# SRAM.net
KiCad netlist of a schematic drawn in Altium Designer
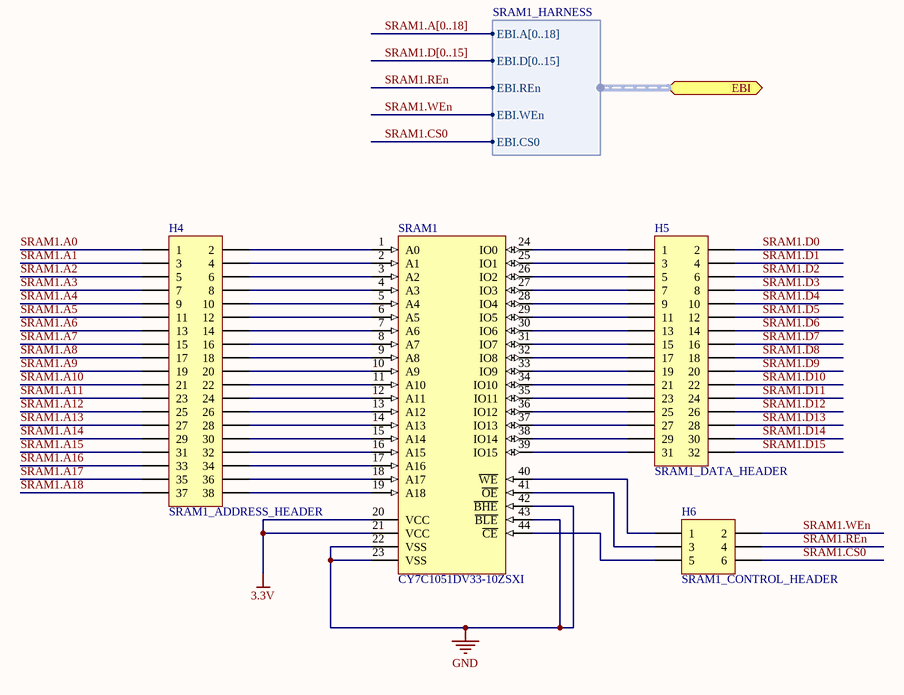
[diagram p0: SRAM.SchDoc]

(export (version "E")
  (design (tool "Eeschema 10.0.6"))
  (components
    (comp (ref "H4")
      (value "SRAM1_ADDRESS_HEADER")
      (footprint "HDR2X19")
      (description "Header, 19-Pin, Dual row")
      (fields (field (name "PUBLISHER") "Altium Limited"))
      (libsource (lib "Miscellaneous Connectors") (part "Header 19X2"))
    )
    (comp (ref "H5")
      (value "SRAM1_DATA_HEADER")
      (footprint "HDR2X16")
      (description "Header, 16-Pin, Dual row")
      (fields (field (name "PUBLISHER") "Altium Limited"))
      (libsource (lib "Miscellaneous Connectors") (part "Header 16X2"))
    )
    (comp (ref "H6")
      (value "SRAM1_CONTROL_HEADER")
      (footprint "HDR2X3")
      (description "Header, 3-Pin, Dual row")
      (fields (field (name "PUBLISHER") "Altium Limited"))
      (libsource (lib "Miscellaneous Connectors") (part "Header 3X2"))
    )
    (comp (ref "SRAM1")
      (value "CY7C1051DV33-10ZSXI")
      (footprint "TSOP-44-SRAM")
      (libsource (lib "Vector Library") (part "CY7C1051DV33-10ZSXI"))
    )
  )
  (nets
    (net (code "3") (name "/SRAM1.A0") (class "Default")
      (node (ref "H4") (pin "1") (pinfunction "1_1") (pintype "passive"))
    )
    (net (code "4") (name "/SRAM1.A1") (class "Default")
      (node (ref "H4") (pin "3") (pinfunction "3_3") (pintype "passive"))
    )
    (net (code "5") (name "/SRAM1.A2") (class "Default")
      (node (ref "H4") (pin "5") (pinfunction "5_5") (pintype "passive"))
    )
    (net (code "6") (name "/SRAM1.A3") (class "Default")
      (node (ref "H4") (pin "7") (pinfunction "7_7") (pintype "passive"))
    )
    (net (code "7") (name "/SRAM1.A4") (class "Default")
      (node (ref "H4") (pin "9") (pinfunction "9_9") (pintype "passive"))
    )
    (net (code "8") (name "/SRAM1.A5") (class "Default")
      (node (ref "H4") (pin "11") (pinfunction "11_11") (pintype "passive"))
    )
    (net (code "9") (name "/SRAM1.A6") (class "Default")
      (node (ref "H4") (pin "13") (pinfunction "13_13") (pintype "passive"))
    )
    (net (code "10") (name "/SRAM1.A7") (class "Default")
      (node (ref "H4") (pin "15") (pinfunction "15_15") (pintype "passive"))
    )
    (net (code "11") (name "/SRAM1.A8") (class "Default")
      (node (ref "H4") (pin "17") (pinfunction "17_17") (pintype "passive"))
    )
    (net (code "12") (name "/SRAM1.A9") (class "Default")
      (node (ref "H4") (pin "19") (pinfunction "19_19") (pintype "passive"))
    )
    (net (code "13") (name "/SRAM1.A10") (class "Default")
      (node (ref "H4") (pin "21") (pinfunction "21_21") (pintype "passive"))
    )
    (net (code "14") (name "/SRAM1.A11") (class "Default")
      (node (ref "H4") (pin "23") (pinfunction "23_23") (pintype "passive"))
    )
    (net (code "15") (name "/SRAM1.A12") (class "Default")
      (node (ref "H4") (pin "25") (pinfunction "25_25") (pintype "passive"))
    )
    (net (code "16") (name "/SRAM1.A13") (class "Default")
      (node (ref "H4") (pin "27") (pinfunction "27_27") (pintype "passive"))
    )
    (net (code "17") (name "/SRAM1.A14") (class "Default")
      (node (ref "H4") (pin "29") (pinfunction "29_29") (pintype "passive"))
    )
    (net (code "18") (name "/SRAM1.A15") (class "Default")
      (node (ref "H4") (pin "31") (pinfunction "31_31") (pintype "passive"))
    )
    (net (code "19") (name "/SRAM1.A16") (class "Default")
      (node (ref "H4") (pin "33") (pinfunction "33_33") (pintype "passive"))
    )
    (net (code "20") (name "/SRAM1.A17") (class "Default")
      (node (ref "H4") (pin "35") (pinfunction "35_35") (pintype "passive"))
    )
    (net (code "21") (name "/SRAM1.A18") (class "Default")
      (node (ref "H4") (pin "37") (pinfunction "37_37") (pintype "passive"))
    )
    (net (code "22") (name "/SRAM1.CS0") (class "Default")
      (node (ref "H6") (pin "6") (pinfunction "6_6") (pintype "passive"))
    )
    (net (code "23") (name "/SRAM1.D0") (class "Default")
      (node (ref "H5") (pin "2") (pinfunction "2_2") (pintype "passive"))
    )
    (net (code "24") (name "/SRAM1.D1") (class "Default")
      (node (ref "H5") (pin "4") (pinfunction "4_4") (pintype "passive"))
    )
    (net (code "25") (name "/SRAM1.D2") (class "Default")
      (node (ref "H5") (pin "6") (pinfunction "6_6") (pintype "passive"))
    )
    (net (code "26") (name "/SRAM1.D3") (class "Default")
      (node (ref "H5") (pin "8") (pinfunction "8_8") (pintype "passive"))
    )
    (net (code "27") (name "/SRAM1.D4") (class "Default")
      (node (ref "H5") (pin "10") (pinfunction "10_10") (pintype "passive"))
    )
    (net (code "28") (name "/SRAM1.D5") (class "Default")
      (node (ref "H5") (pin "12") (pinfunction "12_12") (pintype "passive"))
    )
    (net (code "29") (name "/SRAM1.D6") (class "Default")
      (node (ref "H5") (pin "14") (pinfunction "14_14") (pintype "passive"))
    )
    (net (code "30") (name "/SRAM1.D7") (class "Default")
      (node (ref "H5") (pin "16") (pinfunction "16_16") (pintype "passive"))
    )
    (net (code "31") (name "/SRAM1.D8") (class "Default")
      (node (ref "H5") (pin "18") (pinfunction "18_18") (pintype "passive"))
    )
    (net (code "32") (name "/SRAM1.D9") (class "Default")
      (node (ref "H5") (pin "20") (pinfunction "20_20") (pintype "passive"))
    )
    (net (code "33") (name "/SRAM1.D10") (class "Default")
      (node (ref "H5") (pin "22") (pinfunction "22_22") (pintype "passive"))
    )
    (net (code "34") (name "/SRAM1.D11") (class "Default")
      (node (ref "H5") (pin "24") (pinfunction "24_24") (pintype "passive"))
    )
    (net (code "35") (name "/SRAM1.D12") (class "Default")
      (node (ref "H5") (pin "26") (pinfunction "26_26") (pintype "passive"))
    )
    (net (code "36") (name "/SRAM1.D13") (class "Default")
      (node (ref "H5") (pin "28") (pinfunction "28_28") (pintype "passive"))
    )
    (net (code "37") (name "/SRAM1.D14") (class "Default")
      (node (ref "H5") (pin "30") (pinfunction "30_30") (pintype "passive"))
    )
    (net (code "38") (name "/SRAM1.D15") (class "Default")
      (node (ref "H5") (pin "32") (pinfunction "32_32") (pintype "passive"))
    )
    (net (code "40") (name "/SRAM1.REn") (class "Default")
      (node (ref "H6") (pin "4") (pinfunction "4_4") (pintype "passive"))
    )
    (net (code "41") (name "/SRAM1.WEn") (class "Default")
      (node (ref "H6") (pin "2") (pinfunction "2_2") (pintype "passive"))
    )
    (net (code "43") (name "3.3V") (class "Default")
      (node (ref "SRAM1") (pin "20") (pinfunction "VCC_20") (pintype "power_in"))
      (node (ref "SRAM1") (pin "21") (pinfunction "VCC_21") (pintype "power_in"))
    )
    (net (code "44") (name "GND") (class "Default")
      (node (ref "SRAM1") (pin "22") (pinfunction "VSS_22") (pintype "passive"))
      (node (ref "SRAM1") (pin "23") (pinfunction "VSS_23") (pintype "passive"))
      (node (ref "SRAM1") (pin "42") (pinfunction "~{BHE}_42") (pintype "input"))
      (node (ref "SRAM1") (pin "43") (pinfunction "~{BLE}_43") (pintype "input"))
    )
    (net (code "45") (name "Net-(SRAM1-A0)") (class "Default")
      (node (ref "H4") (pin "2") (pinfunction "2_2") (pintype "passive"))
      (node (ref "SRAM1") (pin "1") (pinfunction "A0_1") (pintype "input"))
    )
    (net (code "46") (name "Net-(SRAM1-A1)") (class "Default")
      (node (ref "H4") (pin "4") (pinfunction "4_4") (pintype "passive"))
      (node (ref "SRAM1") (pin "2") (pinfunction "A1_2") (pintype "input"))
    )
    (net (code "47") (name "Net-(SRAM1-A2)") (class "Default")
      (node (ref "H4") (pin "6") (pinfunction "6_6") (pintype "passive"))
      (node (ref "SRAM1") (pin "3") (pinfunction "A2_3") (pintype "input"))
    )
    (net (code "48") (name "Net-(SRAM1-A3)") (class "Default")
      (node (ref "H4") (pin "8") (pinfunction "8_8") (pintype "passive"))
      (node (ref "SRAM1") (pin "4") (pinfunction "A3_4") (pintype "input"))
    )
    (net (code "49") (name "Net-(SRAM1-A4)") (class "Default")
      (node (ref "H4") (pin "10") (pinfunction "10_10") (pintype "passive"))
      (node (ref "SRAM1") (pin "5") (pinfunction "A4_5") (pintype "input"))
    )
    (net (code "50") (name "Net-(SRAM1-A5)") (class "Default")
      (node (ref "H4") (pin "12") (pinfunction "12_12") (pintype "passive"))
      (node (ref "SRAM1") (pin "6") (pinfunction "A5_6") (pintype "input"))
    )
    (net (code "51") (name "Net-(SRAM1-A6)") (class "Default")
      (node (ref "H4") (pin "14") (pinfunction "14_14") (pintype "passive"))
      (node (ref "SRAM1") (pin "7") (pinfunction "A6_7") (pintype "input"))
    )
    (net (code "52") (name "Net-(SRAM1-A7)") (class "Default")
      (node (ref "H4") (pin "16") (pinfunction "16_16") (pintype "passive"))
      (node (ref "SRAM1") (pin "8") (pinfunction "A7_8") (pintype "input"))
    )
    (net (code "53") (name "Net-(SRAM1-A8)") (class "Default")
      (node (ref "H4") (pin "18") (pinfunction "18_18") (pintype "passive"))
      (node (ref "SRAM1") (pin "9") (pinfunction "A8_9") (pintype "input"))
    )
    (net (code "54") (name "Net-(SRAM1-A9)") (class "Default")
      (node (ref "H4") (pin "20") (pinfunction "20_20") (pintype "passive"))
      (node (ref "SRAM1") (pin "10") (pinfunction "A9_10") (pintype "input"))
    )
    (net (code "55") (name "Net-(SRAM1-A10)") (class "Default")
      (node (ref "H4") (pin "22") (pinfunction "22_22") (pintype "passive"))
      (node (ref "SRAM1") (pin "11") (pinfunction "A10_11") (pintype "input"))
    )
    (net (code "56") (name "Net-(SRAM1-A11)") (class "Default")
      (node (ref "H4") (pin "24") (pinfunction "24_24") (pintype "passive"))
      (node (ref "SRAM1") (pin "12") (pinfunction "A11_12") (pintype "input"))
    )
    (net (code "57") (name "Net-(SRAM1-A12)") (class "Default")
      (node (ref "H4") (pin "26") (pinfunction "26_26") (pintype "passive"))
      (node (ref "SRAM1") (pin "13") (pinfunction "A12_13") (pintype "input"))
    )
    (net (code "58") (name "Net-(SRAM1-A13)") (class "Default")
      (node (ref "H4") (pin "28") (pinfunction "28_28") (pintype "passive"))
      (node (ref "SRAM1") (pin "14") (pinfunction "A13_14") (pintype "input"))
    )
    (net (code "59") (name "Net-(SRAM1-A14)") (class "Default")
      (node (ref "H4") (pin "30") (pinfunction "30_30") (pintype "passive"))
      (node (ref "SRAM1") (pin "15") (pinfunction "A14_15") (pintype "input"))
    )
    (net (code "60") (name "Net-(SRAM1-A15)") (class "Default")
      (node (ref "H4") (pin "32") (pinfunction "32_32") (pintype "passive"))
      (node (ref "SRAM1") (pin "16") (pinfunction "A15_16") (pintype "input"))
    )
    (net (code "61") (name "Net-(SRAM1-A16)") (class "Default")
      (node (ref "H4") (pin "34") (pinfunction "34_34") (pintype "passive"))
      (node (ref "SRAM1") (pin "17") (pinfunction "A16_17") (pintype "input"))
    )
    (net (code "62") (name "Net-(SRAM1-A17)") (class "Default")
      (node (ref "H4") (pin "36") (pinfunction "36_36") (pintype "passive"))
      (node (ref "SRAM1") (pin "18") (pinfunction "A17_18") (pintype "input"))
    )
    (net (code "63") (name "Net-(SRAM1-A18)") (class "Default")
      (node (ref "H4") (pin "38") (pinfunction "38_38") (pintype "passive"))
      (node (ref "SRAM1") (pin "19") (pinfunction "A18_19") (pintype "input"))
    )
    (net (code "64") (name "Net-(SRAM1-IO0)") (class "Default")
      (node (ref "H5") (pin "1") (pinfunction "1_1") (pintype "passive"))
      (node (ref "SRAM1") (pin "24") (pinfunction "IO0_24") (pintype "bidirectional"))
    )
    (net (code "65") (name "Net-(SRAM1-IO1)") (class "Default")
      (node (ref "H5") (pin "3") (pinfunction "3_3") (pintype "passive"))
      (node (ref "SRAM1") (pin "25") (pinfunction "IO1_25") (pintype "bidirectional"))
    )
    (net (code "66") (name "Net-(SRAM1-IO2)") (class "Default")
      (node (ref "H5") (pin "5") (pinfunction "5_5") (pintype "passive"))
      (node (ref "SRAM1") (pin "26") (pinfunction "IO2_26") (pintype "bidirectional"))
    )
    (net (code "67") (name "Net-(SRAM1-IO3)") (class "Default")
      (node (ref "H5") (pin "7") (pinfunction "7_7") (pintype "passive"))
      (node (ref "SRAM1") (pin "27") (pinfunction "IO3_27") (pintype "bidirectional"))
    )
    (net (code "68") (name "Net-(SRAM1-IO4)") (class "Default")
      (node (ref "H5") (pin "9") (pinfunction "9_9") (pintype "passive"))
      (node (ref "SRAM1") (pin "28") (pinfunction "IO4_28") (pintype "bidirectional"))
    )
    (net (code "69") (name "Net-(SRAM1-IO5)") (class "Default")
      (node (ref "H5") (pin "11") (pinfunction "11_11") (pintype "passive"))
      (node (ref "SRAM1") (pin "29") (pinfunction "IO5_29") (pintype "bidirectional"))
    )
    (net (code "70") (name "Net-(SRAM1-IO6)") (class "Default")
      (node (ref "H5") (pin "13") (pinfunction "13_13") (pintype "passive"))
      (node (ref "SRAM1") (pin "30") (pinfunction "IO6_30") (pintype "bidirectional"))
    )
    (net (code "71") (name "Net-(SRAM1-IO7)") (class "Default")
      (node (ref "H5") (pin "15") (pinfunction "15_15") (pintype "passive"))
      (node (ref "SRAM1") (pin "31") (pinfunction "IO7_31") (pintype "bidirectional"))
    )
    (net (code "72") (name "Net-(SRAM1-IO8)") (class "Default")
      (node (ref "H5") (pin "17") (pinfunction "17_17") (pintype "passive"))
      (node (ref "SRAM1") (pin "32") (pinfunction "IO8_32") (pintype "bidirectional"))
    )
    (net (code "73") (name "Net-(SRAM1-IO9)") (class "Default")
      (node (ref "H5") (pin "19") (pinfunction "19_19") (pintype "passive"))
      (node (ref "SRAM1") (pin "33") (pinfunction "IO9_33") (pintype "bidirectional"))
    )
    (net (code "74") (name "Net-(SRAM1-IO10)") (class "Default")
      (node (ref "H5") (pin "21") (pinfunction "21_21") (pintype "passive"))
      (node (ref "SRAM1") (pin "34") (pinfunction "IO10_34") (pintype "bidirectional"))
    )
    (net (code "75") (name "Net-(SRAM1-IO11)") (class "Default")
      (node (ref "H5") (pin "23") (pinfunction "23_23") (pintype "passive"))
      (node (ref "SRAM1") (pin "35") (pinfunction "IO11_35") (pintype "bidirectional"))
    )
    (net (code "76") (name "Net-(SRAM1-IO12)") (class "Default")
      (node (ref "H5") (pin "25") (pinfunction "25_25") (pintype "passive"))
      (node (ref "SRAM1") (pin "36") (pinfunction "IO12_36") (pintype "bidirectional"))
    )
    (net (code "77") (name "Net-(SRAM1-IO13)") (class "Default")
      (node (ref "H5") (pin "27") (pinfunction "27_27") (pintype "passive"))
      (node (ref "SRAM1") (pin "37") (pinfunction "IO13_37") (pintype "bidirectional"))
    )
    (net (code "78") (name "Net-(SRAM1-IO14)") (class "Default")
      (node (ref "H5") (pin "29") (pinfunction "29_29") (pintype "passive"))
      (node (ref "SRAM1") (pin "38") (pinfunction "IO14_38") (pintype "bidirectional"))
    )
    (net (code "79") (name "Net-(SRAM1-IO15)") (class "Default")
      (node (ref "H5") (pin "31") (pinfunction "31_31") (pintype "passive"))
      (node (ref "SRAM1") (pin "39") (pinfunction "IO15_39") (pintype "bidirectional"))
    )
    (net (code "80") (name "Net-(SRAM1-~{CE})") (class "Default")
      (node (ref "H6") (pin "5") (pinfunction "5_5") (pintype "passive"))
      (node (ref "SRAM1") (pin "44") (pinfunction "~{CE}_44") (pintype "input"))
    )
    (net (code "81") (name "Net-(SRAM1-~{OE})") (class "Default")
      (node (ref "H6") (pin "3") (pinfunction "3_3") (pintype "passive"))
      (node (ref "SRAM1") (pin "41") (pinfunction "~{OE}_41") (pintype "input"))
    )
    (net (code "82") (name "Net-(SRAM1-~{WE})") (class "Default")
      (node (ref "H6") (pin "1") (pinfunction "1_1") (pintype "passive"))
      (node (ref "SRAM1") (pin "40") (pinfunction "~{WE}_40") (pintype "input"))
    )
  )
)
